# v10_b.net
KiCad netlist of a schematic drawn in EasyEDA Pro
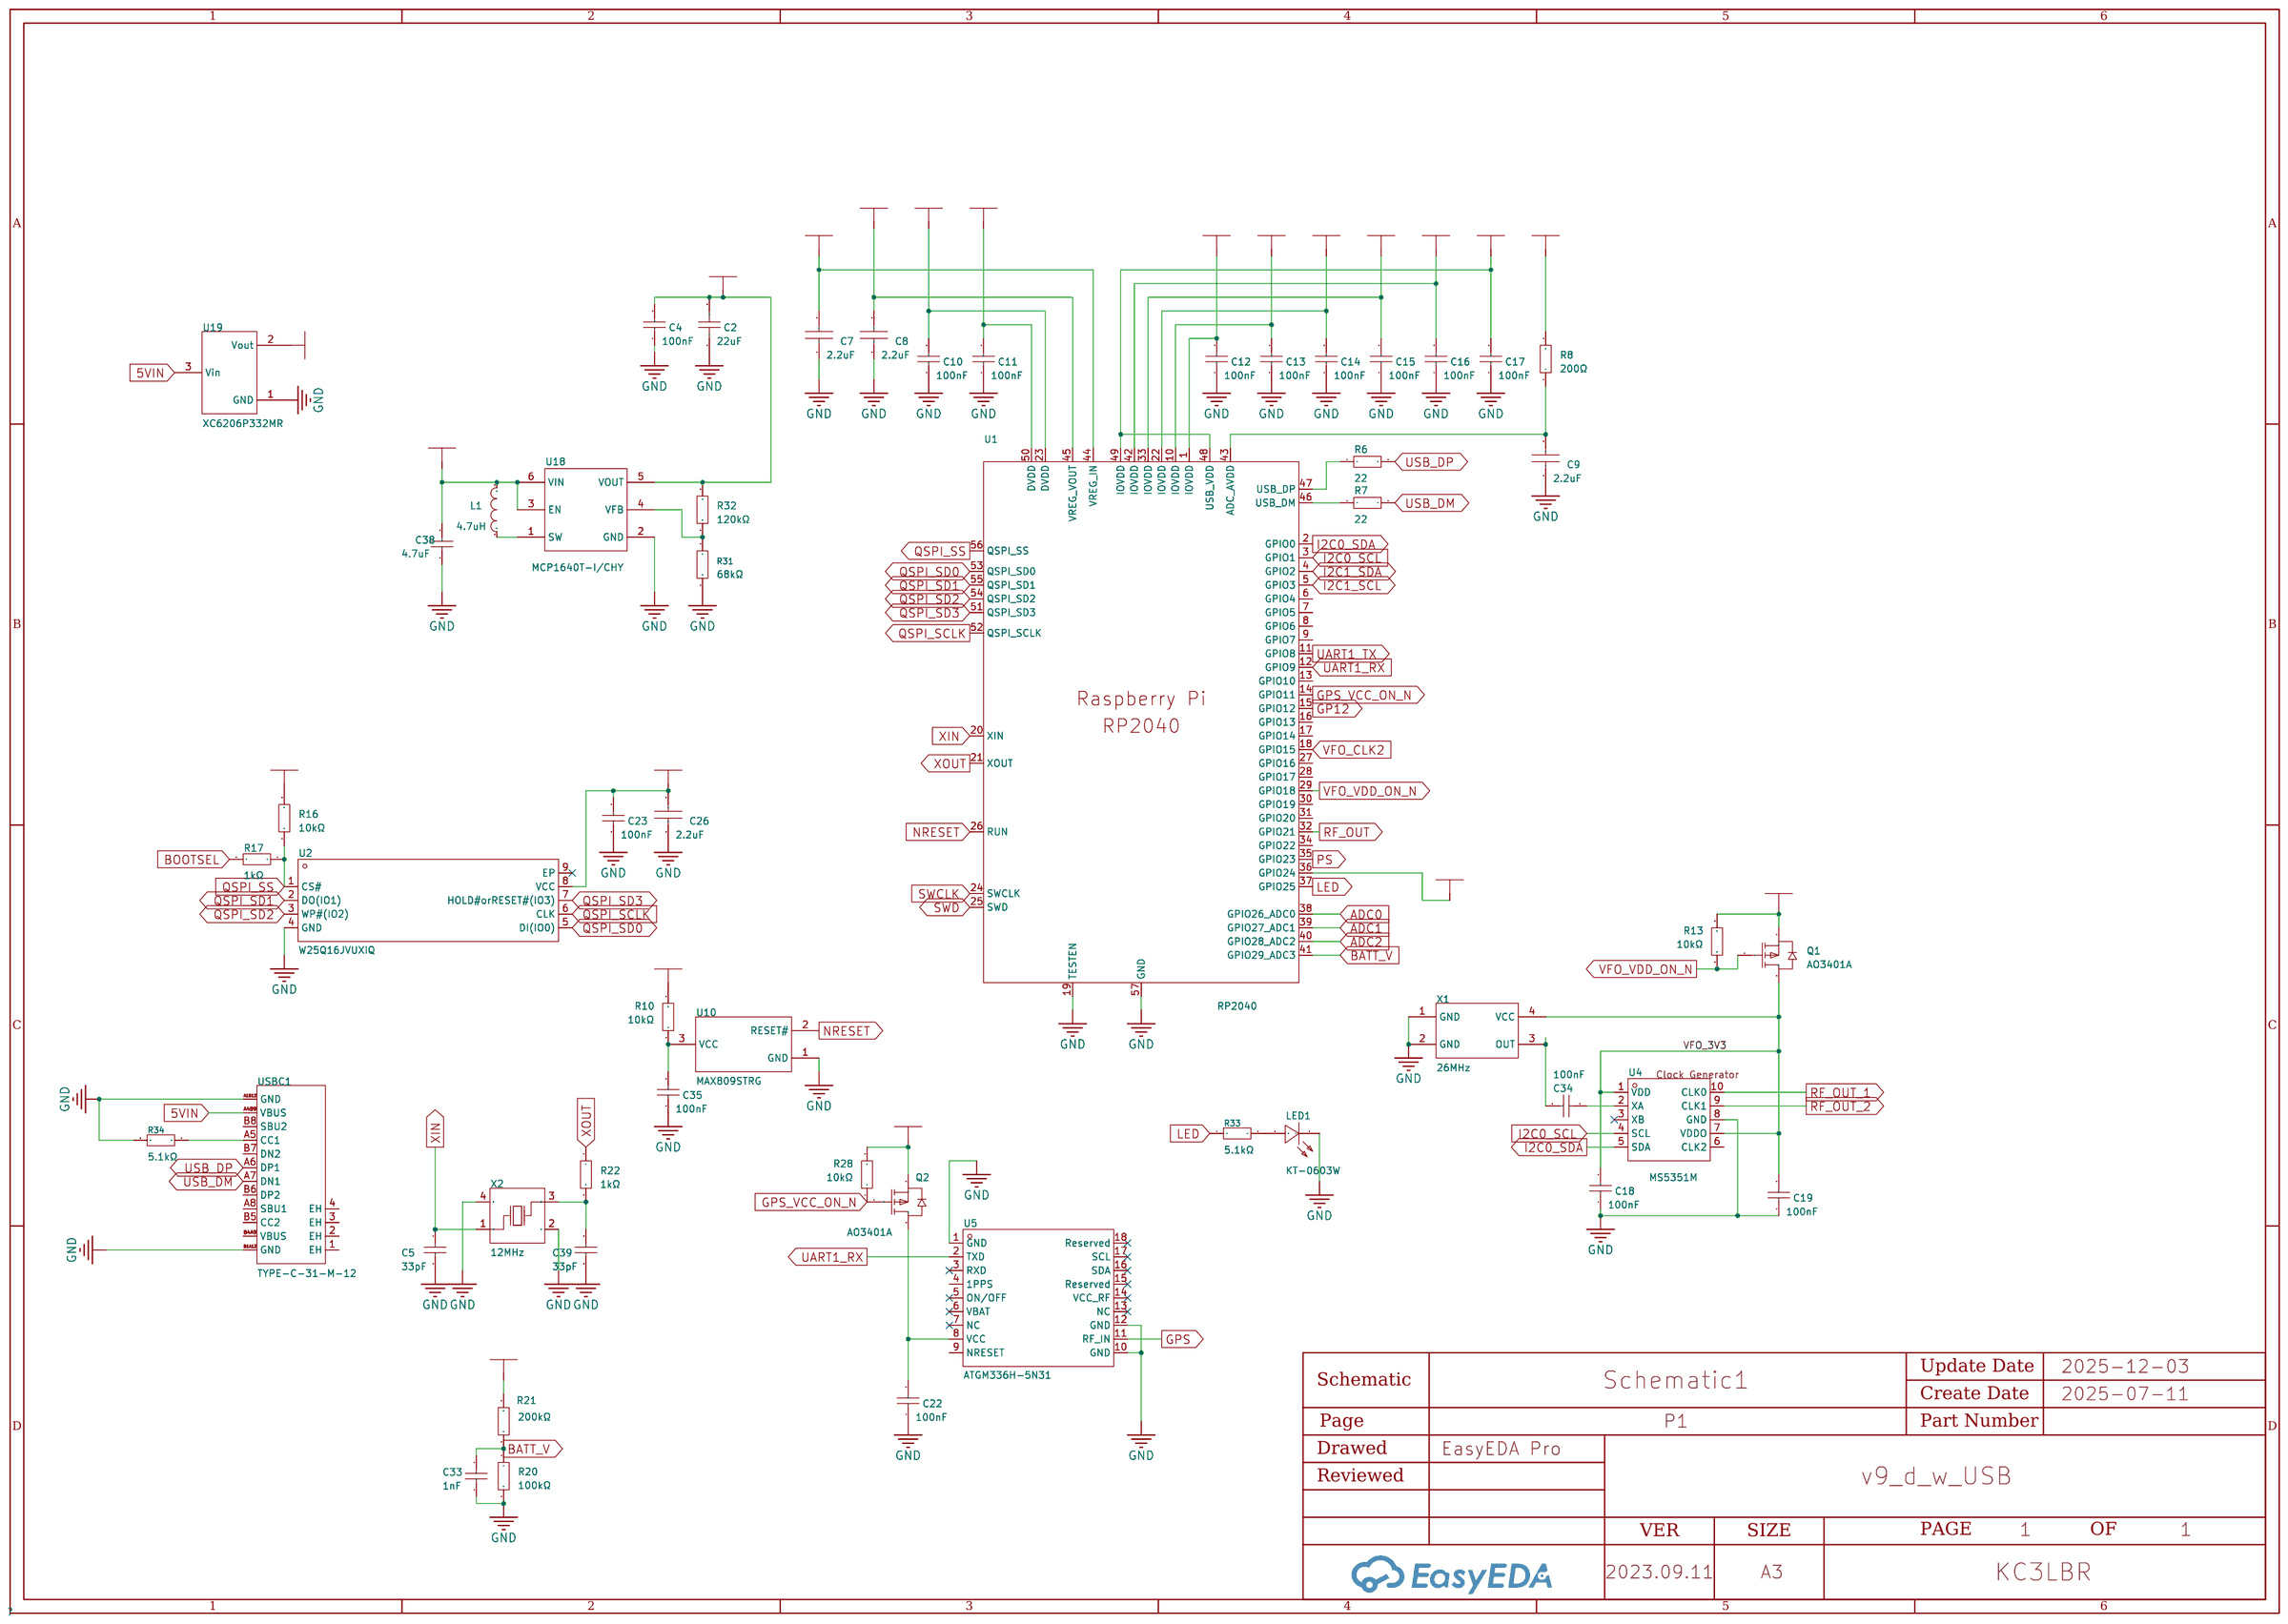
[diagram p0: schematic sheet]

(export (version "E")
  (design (tool "Eeschema 10.0.6"))
  (components
    (comp (ref "C2")
      (value "22uF")
      (footprint "easyedapro:C0603")
      (fields
        (field (name "Manufacturer Part") "CL10A226MQ8NRNC")
        (field (name "Manufacturer") "SAMSUNG(三星)")
      )
      (libsource (lib "easyedapro") (part "CL10A226MQ8NRNC"))
    )
    (comp (ref "C4")
      (value "100nF")
      (footprint "easyedapro:C0402_NEW")
      (fields
        (field (name "Manufacturer Part") "CL05B104KO5NNNC")
        (field (name "Manufacturer") "SAMSUNG(三星)")
      )
      (libsource (lib "easyedapro") (part "CL05B104KO5NNNC"))
    )
    (comp (ref "C5")
      (value "33pF")
      (footprint "easyedapro:C0402")
      (fields (field (name "Manufacturer Part") "0402CG330J500NT") (field (name "Manufacturer") "FH(风华)"))
      (libsource (lib "easyedapro") (part "0402CG330J500NT"))
    )
    (comp (ref "C7")
      (value "2.2uF")
      (footprint "easyedapro:C0402")
      (fields
        (field (name "Manufacturer Part") "CL05A225MQ5NSNC")
        (field (name "Manufacturer") "SAMSUNG(三星)")
      )
      (libsource (lib "easyedapro") (part "CL05A225MQ5NSNC"))
    )
    (comp (ref "C8")
      (value "2.2uF")
      (footprint "easyedapro:C0402")
      (fields
        (field (name "Manufacturer Part") "CL05A225MQ5NSNC")
        (field (name "Manufacturer") "SAMSUNG(三星)")
      )
      (libsource (lib "easyedapro") (part "CL05A225MQ5NSNC"))
    )
    (comp (ref "C9")
      (value "2.2uF")
      (footprint "easyedapro:C0402")
      (fields
        (field (name "Manufacturer Part") "CL05A225MQ5NSNC")
        (field (name "Manufacturer") "SAMSUNG(三星)")
      )
      (libsource (lib "easyedapro") (part "CL05A225MQ5NSNC"))
    )
    (comp (ref "C10")
      (value "100nF")
      (footprint "easyedapro:C0402_NEW")
      (fields
        (field (name "Manufacturer Part") "CL05B104KO5NNNC")
        (field (name "Manufacturer") "SAMSUNG(三星)")
      )
      (libsource (lib "easyedapro") (part "CL05B104KO5NNNC"))
    )
    (comp (ref "C11")
      (value "100nF")
      (footprint "easyedapro:C0402_NEW")
      (fields
        (field (name "Manufacturer Part") "CL05B104KO5NNNC")
        (field (name "Manufacturer") "SAMSUNG(三星)")
      )
      (libsource (lib "easyedapro") (part "CL05B104KO5NNNC"))
    )
    (comp (ref "C12")
      (value "100nF")
      (footprint "easyedapro:C0402_NEW")
      (fields
        (field (name "Manufacturer Part") "CL05B104KO5NNNC")
        (field (name "Manufacturer") "SAMSUNG(三星)")
      )
      (libsource (lib "easyedapro") (part "CL05B104KO5NNNC"))
    )
    (comp (ref "C13")
      (value "100nF")
      (footprint "easyedapro:C0402_NEW")
      (fields
        (field (name "Manufacturer Part") "CL05B104KO5NNNC")
        (field (name "Manufacturer") "SAMSUNG(三星)")
      )
      (libsource (lib "easyedapro") (part "CL05B104KO5NNNC"))
    )
    (comp (ref "C14")
      (value "100nF")
      (footprint "easyedapro:C0402_NEW")
      (fields
        (field (name "Manufacturer Part") "CL05B104KO5NNNC")
        (field (name "Manufacturer") "SAMSUNG(三星)")
      )
      (libsource (lib "easyedapro") (part "CL05B104KO5NNNC"))
    )
    (comp (ref "C15")
      (value "100nF")
      (footprint "easyedapro:C0402_NEW")
      (fields
        (field (name "Manufacturer Part") "CL05B104KO5NNNC")
        (field (name "Manufacturer") "SAMSUNG(三星)")
      )
      (libsource (lib "easyedapro") (part "CL05B104KO5NNNC"))
    )
    (comp (ref "C16")
      (value "100nF")
      (footprint "easyedapro:C0402_NEW")
      (fields
        (field (name "Manufacturer Part") "CL05B104KO5NNNC")
        (field (name "Manufacturer") "SAMSUNG(三星)")
      )
      (libsource (lib "easyedapro") (part "CL05B104KO5NNNC"))
    )
    (comp (ref "C17")
      (value "100nF")
      (footprint "easyedapro:C0402_NEW")
      (fields
        (field (name "Manufacturer Part") "CL05B104KO5NNNC")
        (field (name "Manufacturer") "SAMSUNG(三星)")
      )
      (libsource (lib "easyedapro") (part "CL05B104KO5NNNC"))
    )
    (comp (ref "C18")
      (value "100nF")
      (footprint "easyedapro:C0402_NEW")
      (fields
        (field (name "Manufacturer Part") "CL05B104KO5NNNC")
        (field (name "Manufacturer") "SAMSUNG(三星)")
      )
      (libsource (lib "easyedapro") (part "CL05B104KO5NNNC"))
    )
    (comp (ref "C19")
      (value "100nF")
      (footprint "easyedapro:C0402_NEW")
      (fields
        (field (name "Manufacturer Part") "CL05B104KO5NNNC")
        (field (name "Manufacturer") "SAMSUNG(三星)")
      )
      (libsource (lib "easyedapro") (part "CL05B104KO5NNNC"))
    )
    (comp (ref "C22")
      (value "100nF")
      (footprint "easyedapro:C0402_NEW")
      (fields
        (field (name "Manufacturer Part") "CL05B104KO5NNNC")
        (field (name "Manufacturer") "SAMSUNG(三星)")
      )
      (libsource (lib "easyedapro") (part "CL05B104KO5NNNC"))
    )
    (comp (ref "C23")
      (value "100nF")
      (footprint "easyedapro:C0402_NEW")
      (fields
        (field (name "Manufacturer Part") "CL05B104KO5NNNC")
        (field (name "Manufacturer") "SAMSUNG(三星)")
      )
      (libsource (lib "easyedapro") (part "CL05B104KO5NNNC"))
    )
    (comp (ref "C26")
      (value "2.2uF")
      (footprint "easyedapro:C0402")
      (fields
        (field (name "Manufacturer Part") "CL05A225MQ5NSNC")
        (field (name "Manufacturer") "SAMSUNG(三星)")
      )
      (libsource (lib "easyedapro") (part "CL05A225MQ5NSNC"))
    )
    (comp (ref "C33")
      (value "1nF")
      (footprint "easyedapro:C0402")
      (fields (field (name "Manufacturer Part") "0402B102K500NT") (field (name "Manufacturer") "FH(风华)"))
      (libsource (lib "easyedapro") (part "0402B102K500NT"))
    )
    (comp (ref "C34")
      (value "100nF")
      (footprint "easyedapro:C0402_NEW")
      (fields
        (field (name "Manufacturer Part") "CL05B104KO5NNNC")
        (field (name "Manufacturer") "SAMSUNG(三星)")
      )
      (libsource (lib "easyedapro") (part "CL05B104KO5NNNC"))
    )
    (comp (ref "C35")
      (value "100nF")
      (footprint "easyedapro:C0402_NEW")
      (fields
        (field (name "Manufacturer Part") "CL05B104KO5NNNC")
        (field (name "Manufacturer") "SAMSUNG(三星)")
      )
      (libsource (lib "easyedapro") (part "CL05B104KO5NNNC"))
    )
    (comp (ref "C38")
      (value "4.7uF")
      (footprint "easyedapro:C0603")
      (fields
        (field (name "Manufacturer Part") "CL10A475KO8NNNC")
        (field (name "Manufacturer") "SAMSUNG(三星)")
      )
      (libsource (lib "easyedapro") (part "CL10A475KO8NNNC"))
    )
    (comp (ref "C39")
      (value "33pF")
      (footprint "easyedapro:C0402")
      (fields (field (name "Manufacturer Part") "0402CG330J500NT") (field (name "Manufacturer") "FH(风华)"))
      (libsource (lib "easyedapro") (part "0402CG330J500NT"))
    )
    (comp (ref "L1")
      (value "4.7uH")
      (footprint "easyedapro:IND-SMD_L2.5-W1.8")
      (fields
        (field (name "Manufacturer Part") "CBC2518T4R7M")
        (field (name "Manufacturer") "TAIYO YUDEN(太诱)")
      )
      (libsource (lib "easyedapro") (part "CBC2518T4R7M"))
    )
    (comp (ref "LED1")
      (value "KT-0603W")
      (footprint "easyedapro:LED0603-R-RD_WHITE")
      (fields (field (name "Manufacturer") "KENTO"))
      (libsource (lib "easyedapro") (part "0603White light_C2290"))
    )
    (comp (ref "Q1")
      (value "AO3401A")
      (footprint "easyedapro:SOT-23_L2.9-W1.3-P1.90-LS2.4-BR")
      (fields (field (name "Manufacturer") "AOS"))
      (libsource (lib "easyedapro") (part "AO3401A"))
    )
    (comp (ref "Q2")
      (value "AO3401A")
      (footprint "easyedapro:SOT-23_L2.9-W1.3-P1.90-LS2.4-BR")
      (fields (field (name "Manufacturer") "AOS"))
      (libsource (lib "easyedapro") (part "AO3401A"))
    )
    (comp (ref "R6")
      (value "22")
      (footprint "easyedapro:R0402")
      (fields
        (field (name "Manufacturer Part") "0402WGF220JTCE")
        (field (name "Manufacturer") "UNI-ROYAL(厚声)")
      )
      (libsource (lib "easyedapro") (part "0402WGF220JTCE"))
    )
    (comp (ref "R7")
      (value "22")
      (footprint "easyedapro:R0402")
      (fields
        (field (name "Manufacturer Part") "0402WGF220JTCE")
        (field (name "Manufacturer") "UNI-ROYAL(厚声)")
      )
      (libsource (lib "easyedapro") (part "0402WGF220JTCE"))
    )
    (comp (ref "R8")
      (value "200Ω")
      (footprint "easyedapro:R0402")
      (fields
        (field (name "Manufacturer Part") "0402WGF2000TCE")
        (field (name "Manufacturer") "UNI-ROYAL(厚声)")
      )
      (libsource (lib "easyedapro") (part "0402WGF2000TCE"))
    )
    (comp (ref "R10")
      (value "10kΩ")
      (footprint "easyedapro:R0402")
      (fields
        (field (name "Manufacturer Part") "0402WGF1002TCE")
        (field (name "Manufacturer") "UNI-ROYAL(厚声)")
      )
      (libsource (lib "easyedapro") (part "0402WGF1002TCE"))
    )
    (comp (ref "R13")
      (value "10kΩ")
      (footprint "easyedapro:R0402")
      (fields
        (field (name "Manufacturer Part") "0402WGF1002TCE")
        (field (name "Manufacturer") "UNI-ROYAL(厚声)")
      )
      (libsource (lib "easyedapro") (part "0402WGF1002TCE"))
    )
    (comp (ref "R16")
      (value "10kΩ")
      (footprint "easyedapro:R0402")
      (fields
        (field (name "Manufacturer Part") "0402WGF1002TCE")
        (field (name "Manufacturer") "UNI-ROYAL(厚声)")
      )
      (libsource (lib "easyedapro") (part "0402WGF1002TCE"))
    )
    (comp (ref "R17")
      (value "1kΩ")
      (footprint "easyedapro:R0402")
      (fields
        (field (name "Manufacturer Part") "0402WGF1001TCE")
        (field (name "Manufacturer") "UNI-ROYAL(厚声)")
      )
      (libsource (lib "easyedapro") (part "0402WGF1001TCE"))
    )
    (comp (ref "R20")
      (value "100kΩ")
      (footprint "easyedapro:R0402")
      (fields
        (field (name "Manufacturer Part") "0402WGF1003TCE")
        (field (name "Manufacturer") "UNI-ROYAL(厚声)")
      )
      (libsource (lib "easyedapro") (part "0402WGF1003TCE"))
    )
    (comp (ref "R21")
      (value "200kΩ")
      (footprint "easyedapro:R0402")
      (fields
        (field (name "Manufacturer Part") "0402WGF2003TCE")
        (field (name "Manufacturer") "UNI-ROYAL(厚声)")
      )
      (libsource (lib "easyedapro") (part "0402WGF2003TCE"))
    )
    (comp (ref "R22")
      (value "1kΩ")
      (footprint "easyedapro:R0402")
      (fields
        (field (name "Manufacturer Part") "0402WGF1001TCE")
        (field (name "Manufacturer") "UNI-ROYAL(厚声)")
      )
      (libsource (lib "easyedapro") (part "0402WGF1001TCE"))
    )
    (comp (ref "R28")
      (value "10kΩ")
      (footprint "easyedapro:R0402")
      (fields
        (field (name "Manufacturer Part") "0402WGF1002TCE")
        (field (name "Manufacturer") "UNI-ROYAL(厚声)")
      )
      (libsource (lib "easyedapro") (part "0402WGF1002TCE"))
    )
    (comp (ref "R31")
      (value "68kΩ")
      (footprint "easyedapro:R0603")
      (fields
        (field (name "Manufacturer Part") "0603WAF6802T5E")
        (field (name "Manufacturer") "UNI-ROYAL(厚声)")
      )
      (libsource (lib "easyedapro") (part "0603WAF6802T5E"))
    )
    (comp (ref "R32")
      (value "120kΩ")
      (footprint "easyedapro:R0603")
      (fields
        (field (name "Manufacturer Part") "0603WAF1203T5E")
        (field (name "Manufacturer") "UNI-ROYAL(厚声)")
      )
      (libsource (lib "easyedapro") (part "0603WAF1203T5E"))
    )
    (comp (ref "R33")
      (value "5.1kΩ")
      (footprint "easyedapro:R0402")
      (fields
        (field (name "Manufacturer Part") "0402WGF5101TCE")
        (field (name "Manufacturer") "UNI-ROYAL(厚声)")
      )
      (libsource (lib "easyedapro") (part "0402WGF5101TCE"))
    )
    (comp (ref "R34")
      (value "5.1kΩ")
      (footprint "easyedapro:R0402")
      (fields
        (field (name "Manufacturer Part") "0402WGF5101TCE")
        (field (name "Manufacturer") "UNI-ROYAL(厚声)")
      )
      (libsource (lib "easyedapro") (part "0402WGF5101TCE"))
    )
    (comp (ref "U1")
      (value "RP2040")
      (footprint "easyedapro:LQFN-56_L7.0-W7.0-P0.4-EP")
      (fields (field (name "Manufacturer") "Raspberry Pi(树莓派)"))
      (libsource (lib "easyedapro") (part "RP2040"))
    )
    (comp (ref "U2")
      (value "W25Q16JVUXIQ")
      (footprint "easyedapro:USON-8_L3.0-W2.0-P0.50-BL-EP")
      (fields (field (name "Manufacturer") "WINBOND(华邦)"))
      (libsource (lib "easyedapro") (part "W25Q16JVUXIQ"))
    )
    (comp (ref "U4")
      (value "MS5351M")
      (footprint "easyedapro:MSOP-10_L3.0-W3.0-P0.50-LS5.0-BL")
      (description "Clock Generator")
      (fields (field (name "Manufacturer") "杭州瑞盟"))
      (libsource (lib "easyedapro") (part "MS5351M"))
    )
    (comp (ref "U5")
      (value "ATGM336H-5N31")
      (footprint "easyedapro:GPSM-SMD_ATGM336H-TR")
      (fields (field (name "Manufacturer") "杭州中科微"))
      (libsource (lib "easyedapro") (part "ATGM336H-5N31"))
    )
    (comp (ref "U10")
      (value "MAX809STRG")
      (footprint "easyedapro:SOT-23-3_L2.9-W1.6-P1.90-LS2.8-BR")
      (fields (field (name "Manufacturer") "onsemi(安森美)"))
      (libsource (lib "easyedapro") (part "MAX809STRG"))
    )
    (comp (ref "U18")
      (value "MCP1640T-I/CHY")
      (footprint "easyedapro:SOT-23-6_L2.9-W1.6-P0.95-LS2.8-BR")
      (fields (field (name "Manufacturer") "MICROCHIP(美国微芯)"))
      (libsource (lib "easyedapro") (part "MCP1640T-I/CHY"))
    )
    (comp (ref "U19")
      (value "XC6206P332MR")
      (footprint "easyedapro:SOT-23-3_L2.9-W1.6-P1.90-LS2.8-BR")
      (fields (field (name "Manufacturer") "TOREX(特瑞仕)"))
      (libsource (lib "easyedapro") (part "XC6206P332MR"))
    )
    (comp (ref "USBC1")
      (value "TYPE-C-31-M-12")
      (footprint "easyedapro:USB-C_SMD-TYPE-C-31-M-12_1")
      (fields (field (name "Manufacturer") "韩国韩荣"))
      (libsource (lib "easyedapro") (part "TYPE-C-31-M-12"))
    )
    (comp (ref "X1")
      (value "26MHz")
      (footprint "easyedapro:OSC-SMD_4P-L2.5-W2.0-BL")
      (fields (field (name "Manufacturer Part") "1XXB26000MAA") (field (name "Manufacturer") "KDS(大真空)"))
      (libsource (lib "easyedapro") (part "1XXB26000MAA"))
    )
    (comp (ref "X2")
      (value "12MHz")
      (footprint "easyedapro:OSC-SMD_4P-L3.2-W2.5-BL")
      (fields (field (name "Manufacturer Part") "X322512MSB4SI") (field (name "Manufacturer") "YXC(扬兴晶振)"))
      (libsource (lib "easyedapro") (part "X322512MSB4SI"))
    )
  )
  (nets
    (net (code "1") (name "/VFO_3V3") (class "Default")
      (node (ref "C18") (pin "2") (pinfunction "2_2") (pintype "input"))
      (node (ref "C19") (pin "2") (pinfunction "2_2") (pintype "input"))
      (node (ref "Q1") (pin "3") (pinfunction "D_3") (pintype "input"))
      (node (ref "U4") (pin "1") (pinfunction "VDD_1") (pintype "input"))
      (node (ref "U4") (pin "7") (pinfunction "VDDO_7") (pintype "input"))
      (node (ref "X1") (pin "4") (pinfunction "VCC_4") (pintype "input"))
    )
    (net (code "2") (name "1V1") (class "Default")
      (node (ref "C10") (pin "2") (pinfunction "2_2") (pintype "input"))
      (node (ref "C11") (pin "2") (pinfunction "2_2") (pintype "input"))
      (node (ref "C8") (pin "2") (pinfunction "2_2") (pintype "input"))
      (node (ref "U1") (pin "23") (pinfunction "DVDD_23") (pintype "bidirectional"))
      (node (ref "U1") (pin "45") (pinfunction "VREG_VOUT_45") (pintype "bidirectional"))
      (node (ref "U1") (pin "50") (pinfunction "DVDD_50") (pintype "bidirectional"))
    )
    (net (code "3") (name "3V3") (class "Default")
      (node (ref "C12") (pin "2") (pinfunction "2_2") (pintype "input"))
      (node (ref "C13") (pin "2") (pinfunction "2_2") (pintype "input"))
      (node (ref "C14") (pin "2") (pinfunction "2_2") (pintype "input"))
      (node (ref "C15") (pin "2") (pinfunction "2_2") (pintype "input"))
      (node (ref "C16") (pin "2") (pinfunction "2_2") (pintype "input"))
      (node (ref "C17") (pin "2") (pinfunction "2_2") (pintype "input"))
      (node (ref "C2") (pin "2") (pinfunction "2_2") (pintype "input"))
      (node (ref "C23") (pin "2") (pinfunction "2_2") (pintype "input"))
      (node (ref "C26") (pin "2") (pinfunction "2_2") (pintype "input"))
      (node (ref "C4") (pin "2") (pinfunction "2_2") (pintype "input"))
      (node (ref "C7") (pin "2") (pinfunction "2_2") (pintype "input"))
      (node (ref "Q1") (pin "2") (pinfunction "S_2") (pintype "input"))
      (node (ref "Q2") (pin "2") (pinfunction "S_2") (pintype "input"))
      (node (ref "R10") (pin "2") (pinfunction "2_2") (pintype "input"))
      (node (ref "R13") (pin "2") (pinfunction "2_2") (pintype "input"))
      (node (ref "R16") (pin "2") (pinfunction "2_2") (pintype "input"))
      (node (ref "R28") (pin "2") (pinfunction "2_2") (pintype "input"))
      (node (ref "R32") (pin "2") (pinfunction "2_2") (pintype "input"))
      (node (ref "R8") (pin "2") (pinfunction "2_2") (pintype "input"))
      (node (ref "U1") (pin "1") (pinfunction "IOVDD_1") (pintype "bidirectional"))
      (node (ref "U1") (pin "10") (pinfunction "IOVDD_10") (pintype "bidirectional"))
      (node (ref "U1") (pin "22") (pinfunction "IOVDD_22") (pintype "bidirectional"))
      (node (ref "U1") (pin "33") (pinfunction "IOVDD_33") (pintype "bidirectional"))
      (node (ref "U1") (pin "36") (pinfunction "GPIO24_36") (pintype "bidirectional"))
      (node (ref "U1") (pin "42") (pinfunction "IOVDD_42") (pintype "bidirectional"))
      (node (ref "U1") (pin "44") (pinfunction "VREG_IN_44") (pintype "bidirectional"))
      (node (ref "U1") (pin "48") (pinfunction "USB_VDD_48") (pintype "bidirectional"))
      (node (ref "U1") (pin "49") (pinfunction "IOVDD_49") (pintype "bidirectional"))
      (node (ref "U18") (pin "5") (pinfunction "VOUT_5") (pintype "input"))
      (node (ref "U2") (pin "8") (pinfunction "VCC_8") (pintype "input"))
    )
    (net (code "4") (name "5VIN") (class "Default")
      (node (ref "U19") (pin "3") (pinfunction "Vin_3") (pintype "unspecified"))
      (node (ref "USBC1") (pin "A4B9") (pinfunction "VBUS_A4B9") (pintype "unspecified"))
    )
    (net (code "5") (name "ADC0") (class "Default")
      (node (ref "U1") (pin "38") (pinfunction "GPIO26_ADC0_38") (pintype "bidirectional"))
    )
    (net (code "6") (name "ADC1") (class "Default")
      (node (ref "U1") (pin "39") (pinfunction "GPIO27_ADC1_39") (pintype "bidirectional"))
    )
    (net (code "7") (name "ADC2") (class "Default")
      (node (ref "U1") (pin "40") (pinfunction "GPIO28_ADC2_40") (pintype "bidirectional"))
    )
    (net (code "8") (name "BATT_V") (class "Default")
      (node (ref "C33") (pin "2") (pinfunction "2_2") (pintype "input"))
      (node (ref "R20") (pin "1") (pinfunction "1_1") (pintype "input"))
      (node (ref "R21") (pin "1") (pinfunction "1_1") (pintype "input"))
      (node (ref "U1") (pin "41") (pinfunction "GPIO29_ADC3_41") (pintype "bidirectional"))
    )
    (net (code "9") (name "BOOTSEL") (class "Default")
      (node (ref "R17") (pin "2") (pinfunction "2_2") (pintype "input"))
    )
    (net (code "10") (name "GND") (class "Default")
      (node (ref "C10") (pin "1") (pinfunction "1_1") (pintype "input"))
      (node (ref "C11") (pin "1") (pinfunction "1_1") (pintype "input"))
      (node (ref "C12") (pin "1") (pinfunction "1_1") (pintype "input"))
      (node (ref "C13") (pin "1") (pinfunction "1_1") (pintype "input"))
      (node (ref "C14") (pin "1") (pinfunction "1_1") (pintype "input"))
      (node (ref "C15") (pin "1") (pinfunction "1_1") (pintype "input"))
      (node (ref "C16") (pin "1") (pinfunction "1_1") (pintype "input"))
      (node (ref "C17") (pin "1") (pinfunction "1_1") (pintype "input"))
      (node (ref "C18") (pin "1") (pinfunction "1_1") (pintype "input"))
      (node (ref "C19") (pin "1") (pinfunction "1_1") (pintype "input"))
      (node (ref "C2") (pin "1") (pinfunction "1_1") (pintype "input"))
      (node (ref "C22") (pin "1") (pinfunction "1_1") (pintype "input"))
      (node (ref "C23") (pin "1") (pinfunction "1_1") (pintype "input"))
      (node (ref "C26") (pin "1") (pinfunction "1_1") (pintype "input"))
      (node (ref "C33") (pin "1") (pinfunction "1_1") (pintype "input"))
      (node (ref "C35") (pin "1") (pinfunction "1_1") (pintype "input"))
      (node (ref "C38") (pin "1") (pinfunction "1_1") (pintype "input"))
      (node (ref "C39") (pin "1") (pinfunction "1_1") (pintype "input"))
      (node (ref "C4") (pin "1") (pinfunction "1_1") (pintype "input"))
      (node (ref "C5") (pin "1") (pinfunction "1_1") (pintype "input"))
      (node (ref "C7") (pin "1") (pinfunction "1_1") (pintype "input"))
      (node (ref "C8") (pin "1") (pinfunction "1_1") (pintype "input"))
      (node (ref "C9") (pin "1") (pinfunction "1_1") (pintype "input"))
      (node (ref "LED1") (pin "2") (pinfunction "K_2") (pintype "unspecified"))
      (node (ref "R20") (pin "2") (pinfunction "2_2") (pintype "input"))
      (node (ref "R31") (pin "1") (pinfunction "1_1") (pintype "input"))
      (node (ref "R34") (pin "1") (pinfunction "1_1") (pintype "input"))
      (node (ref "U1") (pin "19") (pinfunction "TESTEN_19") (pintype "input"))
      (node (ref "U1") (pin "57") (pinfunction "GND_57") (pintype "bidirectional"))
      (node (ref "U10") (pin "1") (pinfunction "GND_1") (pintype "input"))
      (node (ref "U18") (pin "2") (pinfunction "GND_2") (pintype "input"))
      (node (ref "U19") (pin "1") (pinfunction "GND_1") (pintype "unspecified"))
      (node (ref "U2") (pin "4") (pinfunction "GND_4") (pintype "input"))
      (node (ref "U4") (pin "8") (pinfunction "GND_8") (pintype "input"))
      (node (ref "U5") (pin "1") (pinfunction "GND_1") (pintype "input"))
      (node (ref "U5") (pin "10") (pinfunction "GND_10") (pintype "input"))
      (node (ref "U5") (pin "12") (pinfunction "GND_12") (pintype "input"))
      (node (ref "USBC1") (pin "A1B12") (pinfunction "GND_A1B12") (pintype "unspecified"))
      (node (ref "USBC1") (pin "B1A12") (pinfunction "GND_B1A12") (pintype "unspecified"))
      (node (ref "X1") (pin "1") (pinfunction "GND_1") (pintype "input"))
      (node (ref "X1") (pin "2") (pinfunction "GND_2") (pintype "input"))
      (node (ref "X2") (pin "2") (pinfunction "GND_2") (pintype "input"))
      (node (ref "X2") (pin "4") (pinfunction "GND_4") (pintype "input"))
    )
    (net (code "11") (name "GP12") (class "Default")
      (node (ref "U1") (pin "15") (pinfunction "GPIO12_15") (pintype "bidirectional"))
    )
    (net (code "12") (name "GPS") (class "Default")
      (node (ref "U5") (pin "11") (pinfunction "RF_IN_11") (pintype "input"))
    )
    (net (code "13") (name "GPS_VCC_ON_N") (class "Default")
      (node (ref "Q2") (pin "1") (pinfunction "G_1") (pintype "input"))
      (node (ref "R28") (pin "1") (pinfunction "1_1") (pintype "input"))
      (node (ref "U1") (pin "14") (pinfunction "GPIO11_14") (pintype "bidirectional"))
    )
    (net (code "14") (name "I2C0_SCL") (class "Default")
      (node (ref "U1") (pin "3") (pinfunction "GPIO1_3") (pintype "bidirectional"))
      (node (ref "U4") (pin "4") (pinfunction "SCL_4") (pintype "input"))
    )
    (net (code "15") (name "I2C0_SDA") (class "Default")
      (node (ref "U1") (pin "2") (pinfunction "GPIO0_2") (pintype "bidirectional"))
      (node (ref "U4") (pin "5") (pinfunction "SDA_5") (pintype "input"))
    )
    (net (code "16") (name "I2C1_SCL") (class "Default")
      (node (ref "U1") (pin "5") (pinfunction "GPIO3_5") (pintype "bidirectional"))
    )
    (net (code "17") (name "I2C1_SDA") (class "Default")
      (node (ref "U1") (pin "4") (pinfunction "GPIO2_4") (pintype "bidirectional"))
    )
    (net (code "18") (name "LED") (class "Default")
      (node (ref "R33") (pin "1") (pinfunction "1_1") (pintype "input"))
      (node (ref "U1") (pin "37") (pinfunction "GPIO25_37") (pintype "bidirectional"))
    )
    (net (code "19") (name "NRESET") (class "Default")
      (node (ref "U1") (pin "26") (pinfunction "RUN_26") (pintype "input"))
      (node (ref "U10") (pin "2") (pinfunction "RESET#_2") (pintype "input"))
    )
    (net (code "20") (name "Net-(LED1-A)") (class "Default")
      (node (ref "LED1") (pin "1") (pinfunction "A_1") (pintype "unspecified"))
      (node (ref "R33") (pin "2") (pinfunction "2_2") (pintype "input"))
    )
    (net (code "21") (name "Net-(Q2-D)") (class "Default")
      (node (ref "C22") (pin "2") (pinfunction "2_2") (pintype "input"))
      (node (ref "Q2") (pin "3") (pinfunction "D_3") (pintype "input"))
      (node (ref "U5") (pin "8") (pinfunction "VCC_8") (pintype "input"))
    )
    (net (code "22") (name "Net-(U1-ADC_AVDD)") (class "Default")
      (node (ref "C9") (pin "2") (pinfunction "2_2") (pintype "input"))
      (node (ref "R8") (pin "1") (pinfunction "1_1") (pintype "input"))
      (node (ref "U1") (pin "43") (pinfunction "ADC_AVDD_43") (pintype "bidirectional"))
    )
    (net (code "23") (name "Net-(U1-USB_DM)") (class "Default")
      (node (ref "R7") (pin "1") (pinfunction "1_1") (pintype "input"))
      (node (ref "U1") (pin "46") (pinfunction "USB_DM_46") (pintype "bidirectional"))
    )
    (net (code "24") (name "Net-(U1-USB_DP)") (class "Default")
      (node (ref "R6") (pin "1") (pinfunction "1_1") (pintype "input"))
      (node (ref "U1") (pin "47") (pinfunction "USB_DP_47") (pintype "bidirectional"))
    )
    (net (code "25") (name "Net-(U4-XA)") (class "Default")
      (node (ref "C34") (pin "1") (pinfunction "1_1") (pintype "input"))
      (node (ref "U4") (pin "2") (pinfunction "XA_2") (pintype "input"))
    )
    (net (code "26") (name "Net-(U10-VCC)") (class "Default")
      (node (ref "C35") (pin "2") (pinfunction "2_2") (pintype "input"))
      (node (ref "R10") (pin "1") (pinfunction "1_1") (pintype "input"))
      (node (ref "U10") (pin "3") (pinfunction "VCC_3") (pintype "input"))
    )
    (net (code "27") (name "Net-(U18-SW)") (class "Default")
      (node (ref "L1") (pin "1") (pinfunction "1_1") (pintype "input"))
      (node (ref "U18") (pin "1") (pinfunction "SW_1") (pintype "input"))
    )
    (net (code "28") (name "Net-(U18-VFB)") (class "Default")
      (node (ref "R31") (pin "2") (pinfunction "2_2") (pintype "input"))
      (node (ref "R32") (pin "1") (pinfunction "1_1") (pintype "input"))
      (node (ref "U18") (pin "4") (pinfunction "VFB_4") (pintype "input"))
    )
    (net (code "29") (name "Net-(USBC1-CC1)") (class "Default")
      (node (ref "R34") (pin "2") (pinfunction "2_2") (pintype "input"))
      (node (ref "USBC1") (pin "A5") (pinfunction "CC1_A5") (pintype "unspecified"))
    )
    (net (code "30") (name "Net-(X1-OUT)") (class "Default")
      (node (ref "C34") (pin "2") (pinfunction "2_2") (pintype "input"))
      (node (ref "X1") (pin "3") (pinfunction "OUT_3") (pintype "input"))
    )
    (net (code "31") (name "Net-(X2-OSC2)") (class "Default")
      (node (ref "C39") (pin "2") (pinfunction "2_2") (pintype "input"))
      (node (ref "R22") (pin "2") (pinfunction "2_2") (pintype "input"))
      (node (ref "X2") (pin "3") (pinfunction "OSC2_3") (pintype "input"))
    )
    (net (code "32") (name "PS") (class "Default")
      (node (ref "U1") (pin "35") (pinfunction "GPIO23_35") (pintype "bidirectional"))
    )
    (net (code "33") (name "QSPI_SCLK") (class "Default")
      (node (ref "U1") (pin "52") (pinfunction "QSPI_SCLK_52") (pintype "output"))
      (node (ref "U2") (pin "6") (pinfunction "CLK_6") (pintype "input"))
    )
    (net (code "34") (name "QSPI_SD0") (class "Default")
      (node (ref "U1") (pin "53") (pinfunction "QSPI_SD0_53") (pintype "bidirectional"))
      (node (ref "U2") (pin "5") (pinfunction "DI(IO0)_5") (pintype "input"))
    )
    (net (code "35") (name "QSPI_SD1") (class "Default")
      (node (ref "U1") (pin "55") (pinfunction "QSPI_SD1_55") (pintype "bidirectional"))
      (node (ref "U2") (pin "2") (pinfunction "DO(IO1)_2") (pintype "input"))
    )
    (net (code "36") (name "QSPI_SD2") (class "Default")
      (node (ref "U1") (pin "54") (pinfunction "QSPI_SD2_54") (pintype "bidirectional"))
      (node (ref "U2") (pin "3") (pinfunction "WP#(IO2)_3") (pintype "input"))
    )
    (net (code "37") (name "QSPI_SD3") (class "Default")
      (node (ref "U1") (pin "51") (pinfunction "QSPI_SD3_51") (pintype "bidirectional"))
      (node (ref "U2") (pin "7") (pinfunction "HOLD#orRESET#(IO3)_7") (pintype "input"))
    )
    (net (code "38") (name "QSPI_SS") (class "Default")
      (node (ref "R16") (pin "1") (pinfunction "1_1") (pintype "input"))
      (node (ref "R17") (pin "1") (pinfunction "1_1") (pintype "input"))
      (node (ref "U1") (pin "56") (pinfunction "QSPI_SS_56") (pintype "bidirectional"))
      (node (ref "U2") (pin "1") (pinfunction "CS#_1") (pintype "input"))
    )
    (net (code "39") (name "RF_OUT") (class "Default")
      (node (ref "U1") (pin "32") (pinfunction "GPIO21_32") (pintype "bidirectional"))
    )
    (net (code "40") (name "RF_OUT_1") (class "Default")
      (node (ref "U4") (pin "10") (pinfunction "CLK0_10") (pintype "input"))
    )
    (net (code "41") (name "RF_OUT_2") (class "Default")
      (node (ref "U4") (pin "9") (pinfunction "CLK1_9") (pintype "input"))
    )
    (net (code "42") (name "SWCLK") (class "Default")
      (node (ref "U1") (pin "24") (pinfunction "SWCLK_24") (pintype "output"))
    )
    (net (code "43") (name "SWD") (class "Default")
      (node (ref "U1") (pin "25") (pinfunction "SWD_25") (pintype "bidirectional"))
    )
    (net (code "44") (name "UART1_RX") (class "Default")
      (node (ref "U1") (pin "12") (pinfunction "GPIO9_12") (pintype "bidirectional"))
      (node (ref "U5") (pin "2") (pinfunction "TXD_2") (pintype "input"))
    )
    (net (code "45") (name "UART1_TX") (class "Default")
      (node (ref "U1") (pin "11") (pinfunction "GPIO8_11") (pintype "bidirectional"))
    )
    (net (code "46") (name "USB_DM") (class "Default")
      (node (ref "R7") (pin "2") (pinfunction "2_2") (pintype "input"))
      (node (ref "USBC1") (pin "A7") (pinfunction "DN1_A7") (pintype "unspecified"))
    )
    (net (code "47") (name "USB_DP") (class "Default")
      (node (ref "R6") (pin "2") (pinfunction "2_2") (pintype "input"))
      (node (ref "USBC1") (pin "A6") (pinfunction "DP1_A6") (pintype "unspecified"))
    )
    (net (code "48") (name "VBUS") (class "Default")
      (node (ref "C38") (pin "2") (pinfunction "2_2") (pintype "input"))
      (node (ref "L1") (pin "2") (pinfunction "2_2") (pintype "input"))
      (node (ref "R21") (pin "2") (pinfunction "2_2") (pintype "input"))
      (node (ref "U18") (pin "3") (pinfunction "EN_3") (pintype "input"))
      (node (ref "U18") (pin "6") (pinfunction "VIN_6") (pintype "input"))
      (node (ref "U19") (pin "2") (pinfunction "Vout_2") (pintype "unspecified"))
    )
    (net (code "49") (name "VFO_CLK2") (class "Default")
      (node (ref "U1") (pin "18") (pinfunction "GPIO15_18") (pintype "bidirectional"))
    )
    (net (code "50") (name "VFO_VDD_ON_N") (class "Default")
      (node (ref "Q1") (pin "1") (pinfunction "G_1") (pintype "input"))
      (node (ref "R13") (pin "1") (pinfunction "1_1") (pintype "input"))
      (node (ref "U1") (pin "29") (pinfunction "GPIO18_29") (pintype "bidirectional"))
    )
    (net (code "51") (name "XIN") (class "Default")
      (node (ref "C5") (pin "2") (pinfunction "2_2") (pintype "input"))
      (node (ref "U1") (pin "20") (pinfunction "XIN_20") (pintype "input"))
      (node (ref "X2") (pin "1") (pinfunction "OSC1_1") (pintype "input"))
    )
    (net (code "52") (name "XOUT") (class "Default")
      (node (ref "R22") (pin "1") (pinfunction "1_1") (pintype "input"))
      (node (ref "U1") (pin "21") (pinfunction "XOUT_21") (pintype "input"))
    )
    (net (code "53") (name "unconnected-(U1-GPIO4-Pad6)") (class "Default")
      (node (ref "U1") (pin "6") (pinfunction "GPIO4_6") (pintype "bidirectional"))
    )
    (net (code "54") (name "unconnected-(U1-GPIO5-Pad7)") (class "Default")
      (node (ref "U1") (pin "7") (pinfunction "GPIO5_7") (pintype "bidirectional"))
    )
    (net (code "55") (name "unconnected-(U1-GPIO6-Pad8)") (class "Default")
      (node (ref "U1") (pin "8") (pinfunction "GPIO6_8") (pintype "bidirectional"))
    )
    (net (code "56") (name "unconnected-(U1-GPIO7-Pad9)") (class "Default")
      (node (ref "U1") (pin "9") (pinfunction "GPIO7_9") (pintype "bidirectional"))
    )
    (net (code "57") (name "unconnected-(U1-GPIO10-Pad13)") (class "Default")
      (node (ref "U1") (pin "13") (pinfunction "GPIO10_13") (pintype "bidirectional"))
    )
    (net (code "58") (name "unconnected-(U1-GPIO13-Pad16)") (class "Default")
      (node (ref "U1") (pin "16") (pinfunction "GPIO13_16") (pintype "bidirectional"))
    )
    (net (code "59") (name "unconnected-(U1-GPIO14-Pad17)") (class "Default")
      (node (ref "U1") (pin "17") (pinfunction "GPIO14_17") (pintype "bidirectional"))
    )
    (net (code "60") (name "unconnected-(U1-GPIO16-Pad27)") (class "Default")
      (node (ref "U1") (pin "27") (pinfunction "GPIO16_27") (pintype "bidirectional"))
    )
    (net (code "61") (name "unconnected-(U1-GPIO17-Pad28)") (class "Default")
      (node (ref "U1") (pin "28") (pinfunction "GPIO17_28") (pintype "bidirectional"))
    )
    (net (code "62") (name "unconnected-(U1-GPIO19-Pad30)") (class "Default")
      (node (ref "U1") (pin "30") (pinfunction "GPIO19_30") (pintype "bidirectional"))
    )
    (net (code "63") (name "unconnected-(U1-GPIO20-Pad31)") (class "Default")
      (node (ref "U1") (pin "31") (pinfunction "GPIO20_31") (pintype "bidirectional"))
    )
    (net (code "64") (name "unconnected-(U1-GPIO22-Pad34)") (class "Default")
      (node (ref "U1") (pin "34") (pinfunction "GPIO22_34") (pintype "bidirectional"))
    )
    (net (code "65") (name "unconnected-(U2-EP-Pad9)") (class "Default")
      (node (ref "U2") (pin "9") (pinfunction "EP_9") (pintype "input+no_connect"))
    )
    (net (code "66") (name "unconnected-(U4-CLK2-Pad6)") (class "Default")
      (node (ref "U4") (pin "6") (pinfunction "CLK2_6") (pintype "input"))
    )
    (net (code "67") (name "unconnected-(U4-XB-Pad3)") (class "Default")
      (node (ref "U4") (pin "3") (pinfunction "XB_3") (pintype "input+no_connect"))
    )
    (net (code "68") (name "unconnected-(U5-1PPS-Pad4)") (class "Default")
      (node (ref "U5") (pin "4") (pinfunction "1PPS_4") (pintype "input"))
    )
    (net (code "69") (name "unconnected-(U5-NC-Pad7)") (class "Default")
      (node (ref "U5") (pin "7") (pinfunction "NC_7") (pintype "input+no_connect"))
    )
    (net (code "70") (name "unconnected-(U5-NC-Pad13)") (class "Default")
      (node (ref "U5") (pin "13") (pinfunction "NC_13") (pintype "input+no_connect"))
    )
    (net (code "71") (name "unconnected-(U5-NRESET-Pad9)") (class "Default")
      (node (ref "U5") (pin "9") (pinfunction "NRESET_9") (pintype "input"))
    )
    (net (code "72") (name "unconnected-(U5-ON{slash}OFF-Pad5)") (class "Default")
      (node (ref "U5") (pin "5") (pinfunction "ON/OFF_5") (pintype "input+no_connect"))
    )
    (net (code "73") (name "unconnected-(U5-RXD-Pad3)") (class "Default")
      (node (ref "U5") (pin "3") (pinfunction "RXD_3") (pintype "input+no_connect"))
    )
    (net (code "74") (name "unconnected-(U5-Reserved-Pad15)") (class "Default")
      (node (ref "U5") (pin "15") (pinfunction "Reserved_15") (pintype "input+no_connect"))
    )
    (net (code "75") (name "unconnected-(U5-Reserved-Pad18)") (class "Default")
      (node (ref "U5") (pin "18") (pinfunction "Reserved_18") (pintype "input+no_connect"))
    )
    (net (code "76") (name "unconnected-(U5-SCL-Pad17)") (class "Default")
      (node (ref "U5") (pin "17") (pinfunction "SCL_17") (pintype "input+no_connect"))
    )
    (net (code "77") (name "unconnected-(U5-SDA-Pad16)") (class "Default")
      (node (ref "U5") (pin "16") (pinfunction "SDA_16") (pintype "input+no_connect"))
    )
    (net (code "78") (name "unconnected-(U5-VBAT-Pad6)") (class "Default")
      (node (ref "U5") (pin "6") (pinfunction "VBAT_6") (pintype "input+no_connect"))
    )
    (net (code "79") (name "unconnected-(U5-VCC_RF-Pad14)") (class "Default")
      (node (ref "U5") (pin "14") (pinfunction "VCC_RF_14") (pintype "input+no_connect"))
    )
    (net (code "80") (name "unconnected-(USBC1-CC2-PadB5)") (class "Default")
      (node (ref "USBC1") (pin "B5") (pinfunction "CC2_B5") (pintype "unspecified"))
    )
    (net (code "81") (name "unconnected-(USBC1-DN2-PadB7)") (class "Default")
      (node (ref "USBC1") (pin "B7") (pinfunction "DN2_B7") (pintype "unspecified"))
    )
    (net (code "82") (name "unconnected-(USBC1-DP2-PadB6)") (class "Default")
      (node (ref "USBC1") (pin "B6") (pinfunction "DP2_B6") (pintype "unspecified"))
    )
    (net (code "83") (name "unconnected-(USBC1-EH-Pad1)") (class "Default")
      (node (ref "USBC1") (pin "1") (pinfunction "EH_1") (pintype "unspecified"))
    )
    (net (code "84") (name "unconnected-(USBC1-EH-Pad2)") (class "Default")
      (node (ref "USBC1") (pin "2") (pinfunction "EH_2") (pintype "unspecified"))
    )
    (net (code "85") (name "unconnected-(USBC1-EH-Pad3)") (class "Default")
      (node (ref "USBC1") (pin "3") (pinfunction "EH_3") (pintype "unspecified"))
    )
    (net (code "86") (name "unconnected-(USBC1-EH-Pad4)") (class "Default")
      (node (ref "USBC1") (pin "4") (pinfunction "EH_4") (pintype "unspecified"))
    )
    (net (code "87") (name "unconnected-(USBC1-SBU1-PadA8)") (class "Default")
      (node (ref "USBC1") (pin "A8") (pinfunction "SBU1_A8") (pintype "unspecified"))
    )
    (net (code "88") (name "unconnected-(USBC1-SBU2-PadB8)") (class "Default")
      (node (ref "USBC1") (pin "B8") (pinfunction "SBU2_B8") (pintype "unspecified"))
    )
    (net (code "89") (name "unconnected-(USBC1-VBUS-PadB4A9)") (class "Default")
      (node (ref "USBC1") (pin "B4A9") (pinfunction "VBUS_B4A9") (pintype "unspecified"))
    )
  )
)
